# Controllable_voltage_outputs.net
KiCad netlist of a schematic drawn in Altium Designer
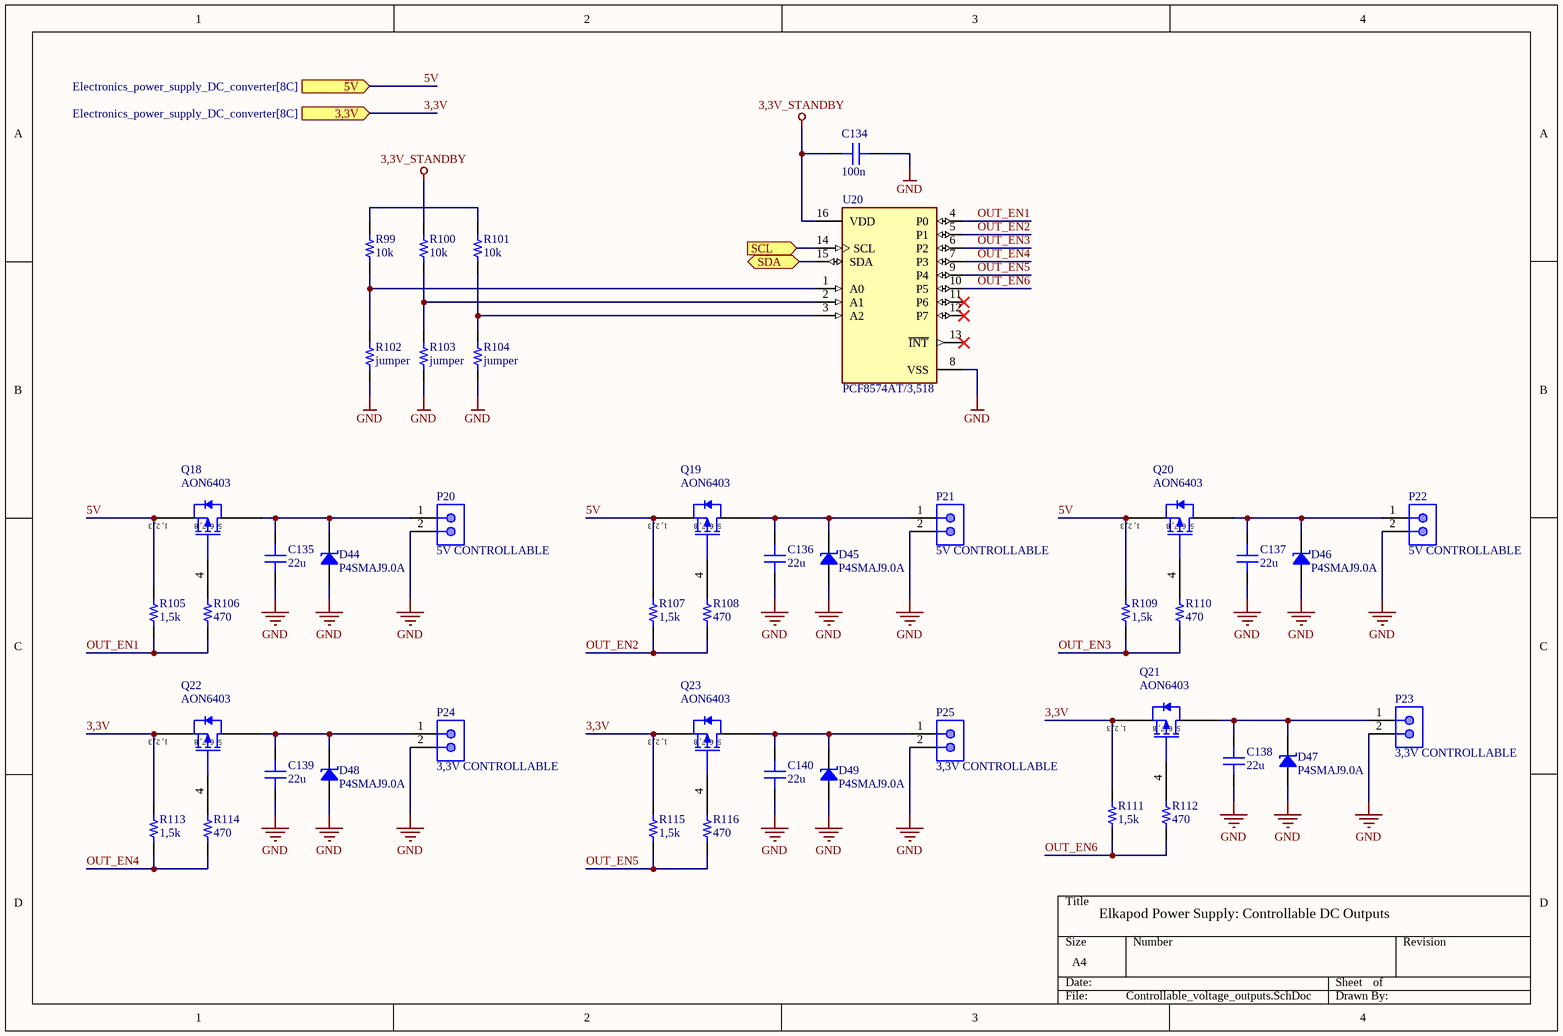
[diagram p0: Controllable_voltage_outputs.SchDoc]

(export (version "E")
  (design (tool "Eeschema 10.0.6"))
  (components
    (comp (ref "C134")
      (value "100n")
      (footprint "CAP 0603_1608")
      (description "CAP CER 100nF 25V X5R 0603")
      (fields (field (name "PART NUMBER") "C0603C272F3GAC7867") (field (name "MANUFACTURER") "KEMET"))
      (libsource (lib "Celestial Altium Library - altium_library") (part "Capacitor"))
    )
    (comp (ref "C135")
      (value "22u")
      (footprint "CAP 0805_2012")
      (description "CAP CER 22UF 25V X7R 0805")
      (fields
        (field (name "PART NUMBER") "VJ0805Y684KXQTW1BC")
        (field (name "MANUFACTURER") "Vishay Vitramon")
      )
      (libsource (lib "Celestial Altium Library - altium_library") (part "Capacitor"))
    )
    (comp (ref "C136")
      (value "22u")
      (footprint "CAP 0805_2012")
      (description "CAP CER 22UF 25V X7R 0805")
      (fields
        (field (name "PART NUMBER") "VJ0805Y684KXQTW1BC")
        (field (name "MANUFACTURER") "Vishay Vitramon")
      )
      (libsource (lib "Celestial Altium Library - altium_library") (part "Capacitor"))
    )
    (comp (ref "C137")
      (value "22u")
      (footprint "CAP 0805_2012")
      (description "CAP CER 22UF 25V X7R 0805")
      (fields
        (field (name "PART NUMBER") "VJ0805Y684KXQTW1BC")
        (field (name "MANUFACTURER") "Vishay Vitramon")
      )
      (libsource (lib "Celestial Altium Library - altium_library") (part "Capacitor"))
    )
    (comp (ref "C138")
      (value "22u")
      (footprint "CAP 0805_2012")
      (description "CAP CER 22UF 25V X7R 0805")
      (fields
        (field (name "PART NUMBER") "VJ0805Y684KXQTW1BC")
        (field (name "MANUFACTURER") "Vishay Vitramon")
      )
      (libsource (lib "Celestial Altium Library - altium_library") (part "Capacitor"))
    )
    (comp (ref "C139")
      (value "22u")
      (footprint "CAP 0805_2012")
      (description "CAP CER 22UF 25V X7R 0805")
      (fields
        (field (name "PART NUMBER") "VJ0805Y684KXQTW1BC")
        (field (name "MANUFACTURER") "Vishay Vitramon")
      )
      (libsource (lib "Celestial Altium Library - altium_library") (part "Capacitor"))
    )
    (comp (ref "C140")
      (value "22u")
      (footprint "CAP 0805_2012")
      (description "CAP CER 22UF 25V X7R 0805")
      (fields
        (field (name "PART NUMBER") "VJ0805Y684KXQTW1BC")
        (field (name "MANUFACTURER") "Vishay Vitramon")
      )
      (libsource (lib "Celestial Altium Library - altium_library") (part "Capacitor"))
    )
    (comp (ref "D44")
      (value "P4SMAJ9.0A")
      (footprint "DO214AC SMA")
      (description "TVS DIODE 9VDC DO214AC")
      (libsource (lib "Celestial Altium Library - altium_library") (part "DIODE TVS UNI"))
    )
    (comp (ref "D45")
      (value "P4SMAJ9.0A")
      (footprint "DO214AC SMA")
      (description "TVS DIODE 9VDC DO214AC")
      (libsource (lib "Celestial Altium Library - altium_library") (part "DIODE TVS UNI"))
    )
    (comp (ref "D46")
      (value "P4SMAJ9.0A")
      (footprint "DO214AC SMA")
      (description "TVS DIODE 9VDC DO214AC")
      (libsource (lib "Celestial Altium Library - altium_library") (part "DIODE TVS UNI"))
    )
    (comp (ref "D47")
      (value "P4SMAJ9.0A")
      (footprint "DO214AC SMA")
      (description "TVS DIODE 9VDC DO214AC")
      (libsource (lib "Celestial Altium Library - altium_library") (part "DIODE TVS UNI"))
    )
    (comp (ref "D48")
      (value "P4SMAJ9.0A")
      (footprint "DO214AC SMA")
      (description "TVS DIODE 9VDC DO214AC")
      (libsource (lib "Celestial Altium Library - altium_library") (part "DIODE TVS UNI"))
    )
    (comp (ref "D49")
      (value "P4SMAJ9.0A")
      (footprint "DO214AC SMA")
      (description "TVS DIODE 9VDC DO214AC")
      (libsource (lib "Celestial Altium Library - altium_library") (part "DIODE TVS UNI"))
    )
    (comp (ref "P20")
      (value "5V CONTROLLABLE")
      (footprint "MOLX-22-23-2021_V")
      (fields (field (name "PARTNUMBER") "22-23-2021"))
      (libsource (lib "Altium Content Vault") (part "CN-1P-M-R2"))
    )
    (comp (ref "P21")
      (value "5V CONTROLLABLE")
      (footprint "MOLX-22-23-2021_V")
      (fields (field (name "PARTNUMBER") "22-23-2021"))
      (libsource (lib "Altium Content Vault") (part "CN-1P-M-R2"))
    )
    (comp (ref "P22")
      (value "5V CONTROLLABLE")
      (footprint "MOLX-22-23-2021_V")
      (fields (field (name "PARTNUMBER") "22-23-2021"))
      (libsource (lib "Altium Content Vault") (part "CN-1P-M-R2"))
    )
    (comp (ref "P23")
      (value "3,3V CONTROLLABLE")
      (footprint "MOLX-22-23-2021_V")
      (fields (field (name "PARTNUMBER") "22-23-2021"))
      (libsource (lib "Altium Content Vault") (part "CN-1P-M-R2"))
    )
    (comp (ref "P24")
      (value "3,3V CONTROLLABLE")
      (footprint "MOLX-22-23-2021_V")
      (fields (field (name "PARTNUMBER") "22-23-2021"))
      (libsource (lib "Altium Content Vault") (part "CN-1P-M-R2"))
    )
    (comp (ref "P25")
      (value "3,3V CONTROLLABLE")
      (footprint "MOLX-22-23-2021_V")
      (fields (field (name "PARTNUMBER") "22-23-2021"))
      (libsource (lib "Altium Content Vault") (part "CN-1P-M-R2"))
    )
    (comp (ref "Q18")
      (value "AON6403")
      (footprint "DFN5x6")
      (description "P-MOSFET; 67A; 30V; DFN5x6")
      (libsource (lib "My_transistors") (part "AON6403"))
    )
    (comp (ref "Q19")
      (value "AON6403")
      (footprint "DFN5x6")
      (description "P-MOSFET; 67A; 30V; DFN5x6")
      (libsource (lib "My_transistors") (part "AON6403"))
    )
    (comp (ref "Q20")
      (value "AON6403")
      (footprint "DFN5x6")
      (description "P-MOSFET; 67A; 30V; DFN5x6")
      (libsource (lib "My_transistors") (part "AON6403"))
    )
    (comp (ref "Q21")
      (value "AON6403")
      (footprint "DFN5x6")
      (description "P-MOSFET; 67A; 30V; DFN5x6")
      (libsource (lib "My_transistors") (part "AON6403"))
    )
    (comp (ref "Q22")
      (value "AON6403")
      (footprint "DFN5x6")
      (description "P-MOSFET; 67A; 30V; DFN5x6")
      (libsource (lib "My_transistors") (part "AON6403"))
    )
    (comp (ref "Q23")
      (value "AON6403")
      (footprint "DFN5x6")
      (description "P-MOSFET; 67A; 30V; DFN5x6")
      (libsource (lib "My_transistors") (part "AON6403"))
    )
    (comp (ref "R99")
      (value "10k")
      (footprint "RES 0603_1608")
      (description "RES 10K OHM 1% 0,1W 0603")
      (fields
        (field (name "PART NUMBER") "RNCS0603BKE10K0")
        (field (name "MANUFACTURER") "Stackpole Electronics Inc")
      )
      (libsource (lib "Celestial Altium Library - altium_library") (part "Resistor"))
    )
    (comp (ref "R100")
      (value "10k")
      (footprint "RES 0603_1608")
      (description "RES 10K OHM 1% 0,1W 0603")
      (fields
        (field (name "PART NUMBER") "RNCS0603BKE10K0")
        (field (name "MANUFACTURER") "Stackpole Electronics Inc")
      )
      (libsource (lib "Celestial Altium Library - altium_library") (part "Resistor"))
    )
    (comp (ref "R101")
      (value "10k")
      (footprint "RES 0603_1608")
      (description "RES 10K OHM 1% 0,1W 0603")
      (fields
        (field (name "PART NUMBER") "RNCS0603BKE10K0")
        (field (name "MANUFACTURER") "Stackpole Electronics Inc")
      )
      (libsource (lib "Celestial Altium Library - altium_library") (part "Resistor"))
    )
    (comp (ref "R102")
      (value "jumper")
      (footprint "RES 0603_1608")
      (description "RES 0 OHM 1% 0,1W 0603")
      (fields
        (field (name "PART NUMBER") "RNCS0603BKE10K0")
        (field (name "MANUFACTURER") "Stackpole Electronics Inc")
      )
      (libsource (lib "Celestial Altium Library - altium_library") (part "Resistor"))
    )
    (comp (ref "R103")
      (value "jumper")
      (footprint "RES 0603_1608")
      (description "RES 0 OHM 1% 0,1W 0603")
      (fields
        (field (name "PART NUMBER") "RNCS0603BKE10K0")
        (field (name "MANUFACTURER") "Stackpole Electronics Inc")
      )
      (libsource (lib "Celestial Altium Library - altium_library") (part "Resistor"))
    )
    (comp (ref "R104")
      (value "jumper")
      (footprint "RES 0603_1608")
      (description "RES 0 OHM 1% 0,1W 0603")
      (fields
        (field (name "PART NUMBER") "RNCS0603BKE10K0")
        (field (name "MANUFACTURER") "Stackpole Electronics Inc")
      )
      (libsource (lib "Celestial Altium Library - altium_library") (part "Resistor"))
    )
    (comp (ref "R105")
      (value "1,5k")
      (footprint "RES 0603_1608")
      (description "RES 1,5K OHM 1% 0,1W 0603")
      (fields
        (field (name "PART NUMBER") "RNCS0603BKE10K0")
        (field (name "MANUFACTURER") "Stackpole Electronics Inc")
      )
      (libsource (lib "Celestial Altium Library - altium_library") (part "Resistor"))
    )
    (comp (ref "R106")
      (value "470")
      (footprint "RES 0603_1608")
      (description "RES 470 OHM 1% 0,1W 0603")
      (fields
        (field (name "PART NUMBER") "RNCS0603BKE10K0")
        (field (name "MANUFACTURER") "Stackpole Electronics Inc")
      )
      (libsource (lib "Celestial Altium Library - altium_library") (part "Resistor"))
    )
    (comp (ref "R107")
      (value "1,5k")
      (footprint "RES 0603_1608")
      (description "RES 1,5K OHM 1% 0,1W 0603")
      (fields
        (field (name "PART NUMBER") "RNCS0603BKE10K0")
        (field (name "MANUFACTURER") "Stackpole Electronics Inc")
      )
      (libsource (lib "Celestial Altium Library - altium_library") (part "Resistor"))
    )
    (comp (ref "R108")
      (value "470")
      (footprint "RES 0603_1608")
      (description "RES 470 OHM 1% 0,1W 0603")
      (fields
        (field (name "PART NUMBER") "RNCS0603BKE10K0")
        (field (name "MANUFACTURER") "Stackpole Electronics Inc")
      )
      (libsource (lib "Celestial Altium Library - altium_library") (part "Resistor"))
    )
    (comp (ref "R109")
      (value "1,5k")
      (footprint "RES 0603_1608")
      (description "RES 1,5K OHM 1% 0,1W 0603")
      (fields
        (field (name "PART NUMBER") "RNCS0603BKE10K0")
        (field (name "MANUFACTURER") "Stackpole Electronics Inc")
      )
      (libsource (lib "Celestial Altium Library - altium_library") (part "Resistor"))
    )
    (comp (ref "R110")
      (value "470")
      (footprint "RES 0603_1608")
      (description "RES 470 OHM 1% 0,1W 0603")
      (fields
        (field (name "PART NUMBER") "RNCS0603BKE10K0")
        (field (name "MANUFACTURER") "Stackpole Electronics Inc")
      )
      (libsource (lib "Celestial Altium Library - altium_library") (part "Resistor"))
    )
    (comp (ref "R111")
      (value "1,5k")
      (footprint "RES 0603_1608")
      (description "RES 1,5K OHM 1% 0,1W 0603")
      (fields
        (field (name "PART NUMBER") "RNCS0603BKE10K0")
        (field (name "MANUFACTURER") "Stackpole Electronics Inc")
      )
      (libsource (lib "Celestial Altium Library - altium_library") (part "Resistor"))
    )
    (comp (ref "R112")
      (value "470")
      (footprint "RES 0603_1608")
      (description "RES 470 OHM 1% 0,1W 0603")
      (fields
        (field (name "PART NUMBER") "RNCS0603BKE10K0")
        (field (name "MANUFACTURER") "Stackpole Electronics Inc")
      )
      (libsource (lib "Celestial Altium Library - altium_library") (part "Resistor"))
    )
    (comp (ref "R113")
      (value "1,5k")
      (footprint "RES 0603_1608")
      (description "RES 1,5K OHM 1% 0,1W 0603")
      (fields
        (field (name "PART NUMBER") "RNCS0603BKE10K0")
        (field (name "MANUFACTURER") "Stackpole Electronics Inc")
      )
      (libsource (lib "Celestial Altium Library - altium_library") (part "Resistor"))
    )
    (comp (ref "R114")
      (value "470")
      (footprint "RES 0603_1608")
      (description "RES 470 OHM 1% 0,1W 0603")
      (fields
        (field (name "PART NUMBER") "RNCS0603BKE10K0")
        (field (name "MANUFACTURER") "Stackpole Electronics Inc")
      )
      (libsource (lib "Celestial Altium Library - altium_library") (part "Resistor"))
    )
    (comp (ref "R115")
      (value "1,5k")
      (footprint "RES 0603_1608")
      (description "RES 1,5K OHM 1% 0,1W 0603")
      (fields
        (field (name "PART NUMBER") "RNCS0603BKE10K0")
        (field (name "MANUFACTURER") "Stackpole Electronics Inc")
      )
      (libsource (lib "Celestial Altium Library - altium_library") (part "Resistor"))
    )
    (comp (ref "R116")
      (value "470")
      (footprint "RES 0603_1608")
      (description "RES 470 OHM 1% 0,1W 0603")
      (fields
        (field (name "PART NUMBER") "RNCS0603BKE10K0")
        (field (name "MANUFACTURER") "Stackpole Electronics Inc")
      )
      (libsource (lib "Celestial Altium Library - altium_library") (part "Resistor"))
    )
    (comp (ref "U20")
      (value "PCF8574AT/3,518")
      (footprint "FP-SOT162-1-MFG")
      (description "IC I/O EXPANDER I2C 8B 16SOIC")
      (fields
        (field (name "MANUFACTURER") "NXP Semiconductors")
        (field (name "OCTOPART") "https://octopart.com/pcf8574at%2F3%2C518-nxp+semiconductors-11541925")
      )
      (libsource (lib "Altium Content Vault") (part "f7fde53ce59de981fb0b266a4e103eb"))
    )
  )
  (nets
    (net (code "1") (name "/3,3V") (class "Default")
      (node (ref "Q21") (pin "1") (pinfunction "S_1") (pintype "passive"))
      (node (ref "Q21") (pin "2") (pinfunction "S_2") (pintype "passive"))
      (node (ref "Q21") (pin "3") (pinfunction "S_3") (pintype "passive"))
      (node (ref "Q22") (pin "1") (pinfunction "S_1") (pintype "passive"))
      (node (ref "Q22") (pin "2") (pinfunction "S_2") (pintype "passive"))
      (node (ref "Q22") (pin "3") (pinfunction "S_3") (pintype "passive"))
      (node (ref "Q23") (pin "1") (pinfunction "S_1") (pintype "passive"))
      (node (ref "Q23") (pin "2") (pinfunction "S_2") (pintype "passive"))
      (node (ref "Q23") (pin "3") (pinfunction "S_3") (pintype "passive"))
      (node (ref "R111") (pin "1") (pinfunction "1_1") (pintype "passive"))
      (node (ref "R113") (pin "1") (pinfunction "1_1") (pintype "passive"))
      (node (ref "R115") (pin "1") (pinfunction "1_1") (pintype "passive"))
    )
    (net (code "2") (name "/5V") (class "Default")
      (node (ref "Q18") (pin "1") (pinfunction "S_1") (pintype "passive"))
      (node (ref "Q18") (pin "2") (pinfunction "S_2") (pintype "passive"))
      (node (ref "Q18") (pin "3") (pinfunction "S_3") (pintype "passive"))
      (node (ref "Q19") (pin "1") (pinfunction "S_1") (pintype "passive"))
      (node (ref "Q19") (pin "2") (pinfunction "S_2") (pintype "passive"))
      (node (ref "Q19") (pin "3") (pinfunction "S_3") (pintype "passive"))
      (node (ref "Q20") (pin "1") (pinfunction "S_1") (pintype "passive"))
      (node (ref "Q20") (pin "2") (pinfunction "S_2") (pintype "passive"))
      (node (ref "Q20") (pin "3") (pinfunction "S_3") (pintype "passive"))
      (node (ref "R105") (pin "1") (pinfunction "1_1") (pintype "passive"))
      (node (ref "R107") (pin "1") (pinfunction "1_1") (pintype "passive"))
      (node (ref "R109") (pin "1") (pinfunction "1_1") (pintype "passive"))
    )
    (net (code "3") (name "/OUT_EN1") (class "Default")
      (node (ref "R105") (pin "2") (pinfunction "2_2") (pintype "passive"))
      (node (ref "R106") (pin "2") (pinfunction "2_2") (pintype "passive"))
      (node (ref "U20") (pin "4") (pinfunction "P0_4") (pintype "bidirectional"))
    )
    (net (code "4") (name "/OUT_EN2") (class "Default")
      (node (ref "R107") (pin "2") (pinfunction "2_2") (pintype "passive"))
      (node (ref "R108") (pin "2") (pinfunction "2_2") (pintype "passive"))
      (node (ref "U20") (pin "5") (pinfunction "P1_5") (pintype "bidirectional"))
    )
    (net (code "5") (name "/OUT_EN3") (class "Default")
      (node (ref "R109") (pin "2") (pinfunction "2_2") (pintype "passive"))
      (node (ref "R110") (pin "2") (pinfunction "2_2") (pintype "passive"))
      (node (ref "U20") (pin "6") (pinfunction "P2_6") (pintype "bidirectional"))
    )
    (net (code "6") (name "/OUT_EN4") (class "Default")
      (node (ref "R113") (pin "2") (pinfunction "2_2") (pintype "passive"))
      (node (ref "R114") (pin "2") (pinfunction "2_2") (pintype "passive"))
      (node (ref "U20") (pin "7") (pinfunction "P3_7") (pintype "bidirectional"))
    )
    (net (code "7") (name "/OUT_EN5") (class "Default")
      (node (ref "R115") (pin "2") (pinfunction "2_2") (pintype "passive"))
      (node (ref "R116") (pin "2") (pinfunction "2_2") (pintype "passive"))
      (node (ref "U20") (pin "9") (pinfunction "P4_9") (pintype "bidirectional"))
    )
    (net (code "8") (name "/OUT_EN6") (class "Default")
      (node (ref "R111") (pin "2") (pinfunction "2_2") (pintype "passive"))
      (node (ref "R112") (pin "2") (pinfunction "2_2") (pintype "passive"))
      (node (ref "U20") (pin "10") (pinfunction "P5_10") (pintype "bidirectional"))
    )
    (net (code "9") (name "/SCL") (class "Default")
      (node (ref "U20") (pin "14") (pinfunction "SCL_14") (pintype "input"))
    )
    (net (code "10") (name "/SDA") (class "Default")
      (node (ref "U20") (pin "15") (pinfunction "SDA_15") (pintype "bidirectional"))
    )
    (net (code "11") (name "3,3V_STANDBY") (class "Default")
      (node (ref "C134") (pin "2") (pinfunction "2_2") (pintype "passive"))
      (node (ref "R100") (pin "1") (pinfunction "1_1") (pintype "passive"))
      (node (ref "U20") (pin "16") (pinfunction "VDD_16") (pintype "power_in"))
    )
    (net (code "12") (name "GND") (class "Default")
      (node (ref "C134") (pin "1") (pinfunction "1_1") (pintype "passive"))
      (node (ref "C135") (pin "1") (pinfunction "1_1") (pintype "passive"))
      (node (ref "C136") (pin "1") (pinfunction "1_1") (pintype "passive"))
      (node (ref "C137") (pin "1") (pinfunction "1_1") (pintype "passive"))
      (node (ref "C138") (pin "1") (pinfunction "1_1") (pintype "passive"))
      (node (ref "C139") (pin "1") (pinfunction "1_1") (pintype "passive"))
      (node (ref "C140") (pin "1") (pinfunction "1_1") (pintype "passive"))
      (node (ref "D44") (pin "1") (pinfunction "1_1") (pintype "passive"))
      (node (ref "D45") (pin "1") (pinfunction "1_1") (pintype "passive"))
      (node (ref "D46") (pin "1") (pinfunction "1_1") (pintype "passive"))
      (node (ref "D47") (pin "1") (pinfunction "1_1") (pintype "passive"))
      (node (ref "D48") (pin "1") (pinfunction "1_1") (pintype "passive"))
      (node (ref "D49") (pin "1") (pinfunction "1_1") (pintype "passive"))
      (node (ref "P20") (pin "2") (pinfunction "2_2") (pintype "passive"))
      (node (ref "P21") (pin "2") (pinfunction "2_2") (pintype "passive"))
      (node (ref "P22") (pin "2") (pinfunction "2_2") (pintype "passive"))
      (node (ref "P23") (pin "2") (pinfunction "2_2") (pintype "passive"))
      (node (ref "P24") (pin "2") (pinfunction "2_2") (pintype "passive"))
      (node (ref "P25") (pin "2") (pinfunction "2_2") (pintype "passive"))
      (node (ref "R102") (pin "2") (pinfunction "2_2") (pintype "passive"))
      (node (ref "R103") (pin "2") (pinfunction "2_2") (pintype "passive"))
      (node (ref "R104") (pin "2") (pinfunction "2_2") (pintype "passive"))
      (node (ref "U20") (pin "8") (pinfunction "VSS_8") (pintype "power_in"))
    )
    (net (code "13") (name "Net-(Q18-D)") (class "Default")
      (node (ref "C135") (pin "2") (pinfunction "2_2") (pintype "passive"))
      (node (ref "D44") (pin "2") (pinfunction "2_2") (pintype "passive"))
      (node (ref "P20") (pin "1") (pinfunction "1_1") (pintype "passive"))
      (node (ref "Q18") (pin "5-6-7-8") (pinfunction "D_5-6-7-8") (pintype "passive"))
    )
    (net (code "14") (name "Net-(Q18-G)") (class "Default")
      (node (ref "Q18") (pin "4") (pinfunction "G_4") (pintype "passive"))
      (node (ref "R106") (pin "1") (pinfunction "1_1") (pintype "passive"))
    )
    (net (code "15") (name "Net-(Q19-D)") (class "Default")
      (node (ref "C136") (pin "2") (pinfunction "2_2") (pintype "passive"))
      (node (ref "D45") (pin "2") (pinfunction "2_2") (pintype "passive"))
      (node (ref "P21") (pin "1") (pinfunction "1_1") (pintype "passive"))
      (node (ref "Q19") (pin "5-6-7-8") (pinfunction "D_5-6-7-8") (pintype "passive"))
    )
    (net (code "16") (name "Net-(Q19-G)") (class "Default")
      (node (ref "Q19") (pin "4") (pinfunction "G_4") (pintype "passive"))
      (node (ref "R108") (pin "1") (pinfunction "1_1") (pintype "passive"))
    )
    (net (code "17") (name "Net-(Q20-D)") (class "Default")
      (node (ref "C137") (pin "2") (pinfunction "2_2") (pintype "passive"))
      (node (ref "D46") (pin "2") (pinfunction "2_2") (pintype "passive"))
      (node (ref "P22") (pin "1") (pinfunction "1_1") (pintype "passive"))
      (node (ref "Q20") (pin "5-6-7-8") (pinfunction "D_5-6-7-8") (pintype "passive"))
    )
    (net (code "18") (name "Net-(Q20-G)") (class "Default")
      (node (ref "Q20") (pin "4") (pinfunction "G_4") (pintype "passive"))
      (node (ref "R110") (pin "1") (pinfunction "1_1") (pintype "passive"))
    )
    (net (code "19") (name "Net-(Q21-D)") (class "Default")
      (node (ref "C138") (pin "2") (pinfunction "2_2") (pintype "passive"))
      (node (ref "D47") (pin "2") (pinfunction "2_2") (pintype "passive"))
      (node (ref "P23") (pin "1") (pinfunction "1_1") (pintype "passive"))
      (node (ref "Q21") (pin "5-6-7-8") (pinfunction "D_5-6-7-8") (pintype "passive"))
    )
    (net (code "20") (name "Net-(Q21-G)") (class "Default")
      (node (ref "Q21") (pin "4") (pinfunction "G_4") (pintype "passive"))
      (node (ref "R112") (pin "1") (pinfunction "1_1") (pintype "passive"))
    )
    (net (code "21") (name "Net-(Q22-D)") (class "Default")
      (node (ref "C139") (pin "2") (pinfunction "2_2") (pintype "passive"))
      (node (ref "D48") (pin "2") (pinfunction "2_2") (pintype "passive"))
      (node (ref "P24") (pin "1") (pinfunction "1_1") (pintype "passive"))
      (node (ref "Q22") (pin "5-6-7-8") (pinfunction "D_5-6-7-8") (pintype "passive"))
    )
    (net (code "22") (name "Net-(Q22-G)") (class "Default")
      (node (ref "Q22") (pin "4") (pinfunction "G_4") (pintype "passive"))
      (node (ref "R114") (pin "1") (pinfunction "1_1") (pintype "passive"))
    )
    (net (code "23") (name "Net-(Q23-D)") (class "Default")
      (node (ref "C140") (pin "2") (pinfunction "2_2") (pintype "passive"))
      (node (ref "D49") (pin "2") (pinfunction "2_2") (pintype "passive"))
      (node (ref "P25") (pin "1") (pinfunction "1_1") (pintype "passive"))
      (node (ref "Q23") (pin "5-6-7-8") (pinfunction "D_5-6-7-8") (pintype "passive"))
    )
    (net (code "24") (name "Net-(Q23-G)") (class "Default")
      (node (ref "Q23") (pin "4") (pinfunction "G_4") (pintype "passive"))
      (node (ref "R116") (pin "1") (pinfunction "1_1") (pintype "passive"))
    )
    (net (code "25") (name "Net-(R101-Pad1)") (class "Default")
      (node (ref "R101") (pin "1") (pinfunction "1_1") (pintype "passive"))
      (node (ref "R99") (pin "1") (pinfunction "1_1") (pintype "passive"))
    )
    (net (code "26") (name "Net-(U20-A0)") (class "Default")
      (node (ref "R102") (pin "1") (pinfunction "1_1") (pintype "passive"))
      (node (ref "R99") (pin "2") (pinfunction "2_2") (pintype "passive"))
      (node (ref "U20") (pin "1") (pinfunction "A0_1") (pintype "input"))
    )
    (net (code "27") (name "Net-(U20-A1)") (class "Default")
      (node (ref "R100") (pin "2") (pinfunction "2_2") (pintype "passive"))
      (node (ref "R103") (pin "1") (pinfunction "1_1") (pintype "passive"))
      (node (ref "U20") (pin "2") (pinfunction "A1_2") (pintype "input"))
    )
    (net (code "28") (name "Net-(U20-A2)") (class "Default")
      (node (ref "R101") (pin "2") (pinfunction "2_2") (pintype "passive"))
      (node (ref "R104") (pin "1") (pinfunction "1_1") (pintype "passive"))
      (node (ref "U20") (pin "3") (pinfunction "A2_3") (pintype "input"))
    )
    (net (code "29") (name "unconnected-(U20-P6-Pad11)") (class "Default")
      (node (ref "U20") (pin "11") (pinfunction "P6_11") (pintype "bidirectional+no_connect"))
    )
    (net (code "30") (name "unconnected-(U20-P7-Pad12)") (class "Default")
      (node (ref "U20") (pin "12") (pinfunction "P7_12") (pintype "bidirectional+no_connect"))
    )
    (net (code "31") (name "unconnected-(U20-~{INT}-Pad13)") (class "Default")
      (node (ref "U20") (pin "13") (pinfunction "~{INT}_13") (pintype "output+no_connect"))
    )
  )
)
